# ADC-EXTERNAL_CLOCK_INPUT.net
KiCad netlist of a schematic drawn in Altium Designer
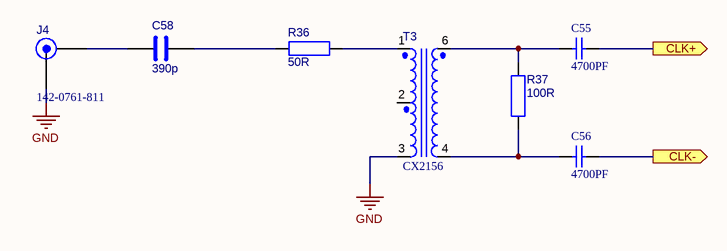
[diagram p0: ADC-EXTERNAL CLOCK INPUT.SchDoc]

(export (version "E")
  (design (tool "Eeschema 10.0.6"))
  (components
    (comp (ref "C55")
      (value "4700PF")
      (footprint "CAPC1005X55N")
      (description "Capacitor 0402 SMD")
      (fields (field (name "CREATED_BY") "EDA-ASA") (field (name "CHECKED_BY") "*"))
      (libsource (lib "EDA-Passive") (part "cap0402"))
    )
    (comp (ref "C56")
      (value "4700PF")
      (footprint "CAPC1005X55N")
      (description "Capacitor 0402 SMD")
      (fields (field (name "CREATED_BY") "EDA-ASA") (field (name "CHECKED_BY") "*"))
      (libsource (lib "EDA-Passive") (part "cap0402"))
    )
    (comp (ref "C58")
      (value "390p")
      (footprint "CAPC1005X55N")
      (description "CAP SMD 0603")
      (fields (field (name "CREATED_BY") "*") (field (name "CHECKED_BY") "*"))
      (libsource (lib "Abdus-TEMP") (part "CAP-0603"))
    )
    (comp (ref "J4")
      (value "~")
      (footprint "EDGE_LAUNCH_TH_SMA")
      (description "High Frequency SMA End Lauch Connector")
      (fields
        (field (name "MANUFACTURER") "JOHNSON")
        (field (name "VOLTAGE") "???")
        (field (name "MANUFACTURER_PN") "142-0761-811")
        (field (name "CREATED_BY") "CT")
        (field (name "CHECKED_BY") "*")
      )
      (libsource (lib "Charles-TEMP") (part "142-0761-811"))
    )
    (comp (ref "R36")
      (value "50R")
      (footprint "RESC1005X40N")
      (description "RESISTOR SMD 0805")
      (fields (field (name "CREATED_BY") "*") (field (name "CHECKED_BY") "NN"))
      (libsource (lib "EDA_Passive") (part "RES-0805"))
    )
    (comp (ref "R37")
      (value "100R")
      (footprint "RESC1005X40N")
      (description "RESISTOR SMD 0805")
      (fields (field (name "CREATED_BY") "*") (field (name "CHECKED_BY") "NN"))
      (libsource (lib "EDA_Passive") (part "RES-0805"))
    )
    (comp (ref "T3")
      (value "CX2156")
      (footprint "PULSE_KAYAK")
      (description "TRANSFORMER WIDEBAND RF APPLICATION")
      (fields
        (field (name "VOLTAGE") "???")
        (field (name "MANUFACTURER_PN") "CX2156")
        (field (name "CREATED_BY") "*")
        (field (name "CHECKED_BY") "*")
      )
      (libsource (lib "Charles-TEMP") (part "CX2156"))
    )
  )
  (nets
    (net (code "1") (name "/CLK+") (class "Default")
      (node (ref "C55") (pin "2") (pinfunction "2_2") (pintype "passive"))
    )
    (net (code "2") (name "/CLK-") (class "Default")
      (node (ref "C56") (pin "2") (pinfunction "2_2") (pintype "passive"))
    )
    (net (code "3") (name "GND") (class "Default")
      (node (ref "J4") (pin "2") (pinfunction "2_2") (pintype "passive"))
      (node (ref "T3") (pin "3") (pinfunction "3_3") (pintype "passive"))
    )
    (net (code "4") (name "Net-(C55-Pad1)") (class "Default")
      (node (ref "C55") (pin "1") (pinfunction "1_1") (pintype "passive"))
      (node (ref "R37") (pin "1") (pinfunction "1_1") (pintype "passive"))
      (node (ref "T3") (pin "6") (pinfunction "6_6") (pintype "passive"))
    )
    (net (code "5") (name "Net-(C56-Pad1)") (class "Default")
      (node (ref "C56") (pin "1") (pinfunction "1_1") (pintype "passive"))
      (node (ref "R37") (pin "2") (pinfunction "2_2") (pintype "passive"))
      (node (ref "T3") (pin "4") (pinfunction "4_4") (pintype "passive"))
    )
    (net (code "6") (name "Net-(C58-Pad1)") (class "Default")
      (node (ref "C58") (pin "1") (pinfunction "1_1") (pintype "passive"))
      (node (ref "J4") (pin "1") (pinfunction "1_1") (pintype "passive"))
    )
    (net (code "7") (name "Net-(C58-Pad2)") (class "Default")
      (node (ref "C58") (pin "2") (pinfunction "2_2") (pintype "passive"))
      (node (ref "R36") (pin "1") (pinfunction "1_1") (pintype "passive"))
    )
    (net (code "8") (name "Net-(R36-Pad2)") (class "Default")
      (node (ref "R36") (pin "2") (pinfunction "2_2") (pintype "passive"))
      (node (ref "T3") (pin "1") (pinfunction "1_1") (pintype "passive"))
    )
    (net (code "9") (name "unconnected-(T3-Pad2)") (class "Default")
      (node (ref "T3") (pin "2") (pinfunction "2_2") (pintype "passive"))
    )
  )
)
